# Audio.net
KiCad netlist of a schematic drawn in Altium Designer
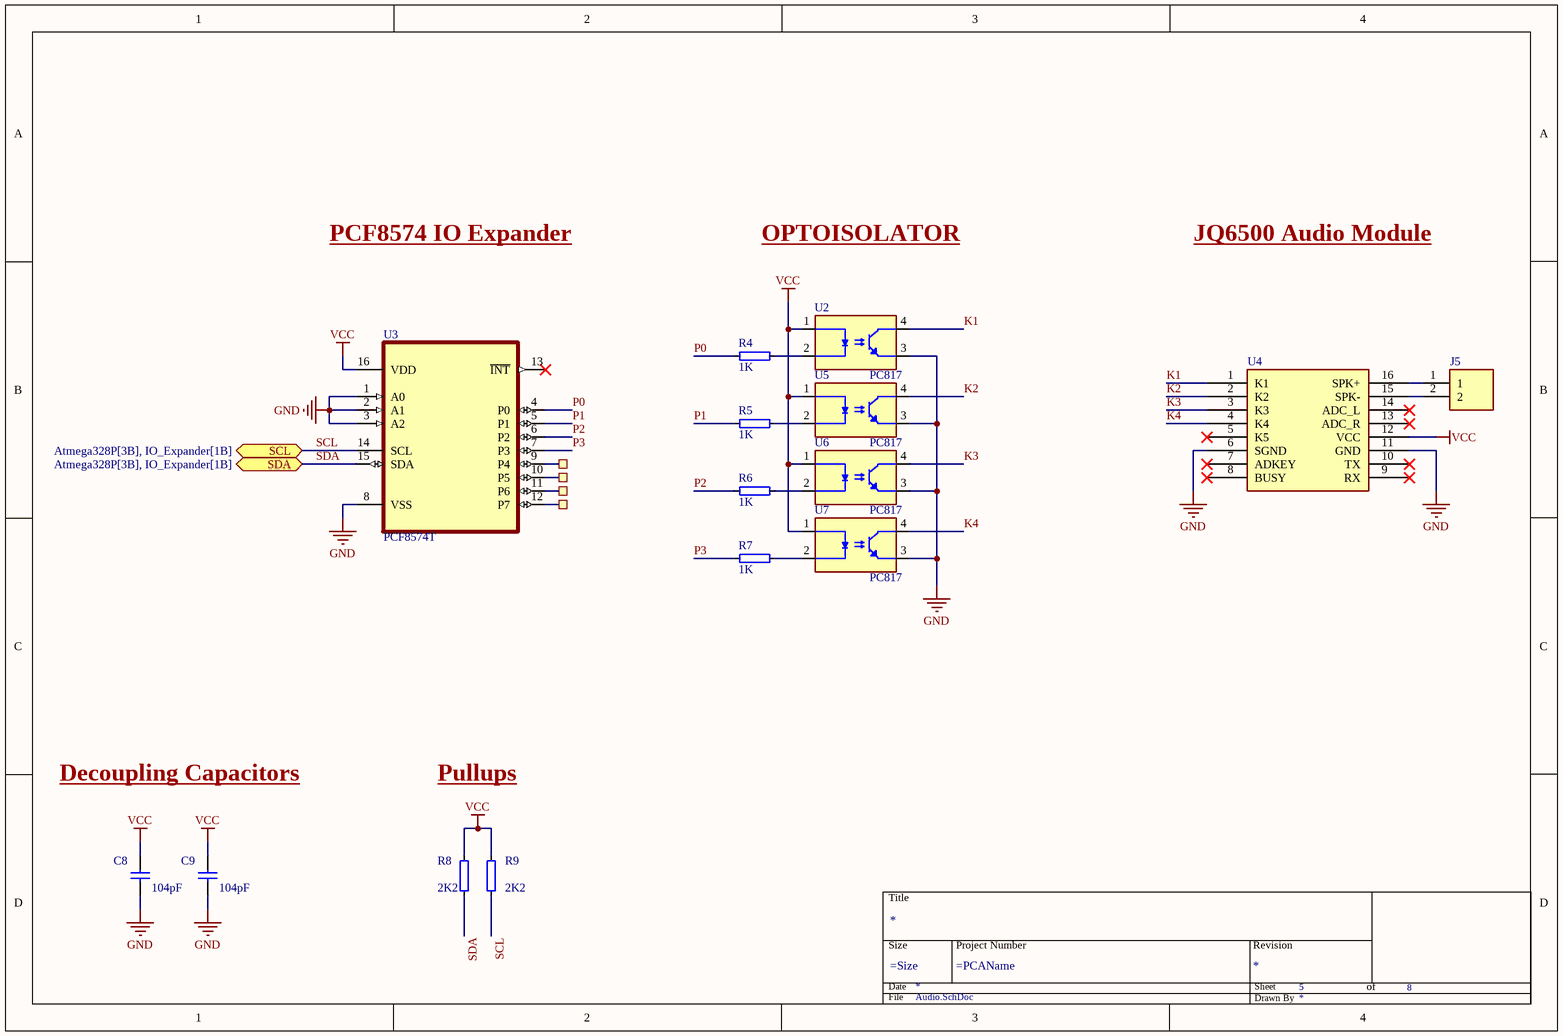
[diagram p0: Audio.SchDoc]

(export (version "E")
  (design (tool "Eeschema 10.0.6"))
  (components
    (comp (ref "*") (value "Title Block") (libsource (lib "HEPA_LIB") (part "Title Block")))
    (comp (ref "C8")
      (value "104pF")
      (footprint "CAPC2012X140N")
      (fields (field (name "PART NUMBER") "CAP_0805") (field (name "PUBLISHER") "Metal Circuits"))
      (libsource (lib "HEPA_LIB") (part "CAP_0805"))
    )
    (comp (ref "C9")
      (value "104pF")
      (footprint "CAPC2012X140N")
      (fields (field (name "PART NUMBER") "CAP_0805") (field (name "PUBLISHER") "Metal Circuits"))
      (libsource (lib "HEPA_LIB") (part "CAP_0805"))
    )
    (comp (ref "J5")
      (value "CONN HEADER VERT 2POS 2.5MM")
      (footprint "JST_B2B-XH-A(LF)(SN)")
      (description "Connector Header Through Hole 2 position 0.098\" (2.50mm)")
      (fields
        (field (name "PART NUMBER") "B2B-XH-A(LF)(SN)")
        (field (name "MANUFACTURER") "JST Sales America Inc.")
        (field (name "PUBLISHER") "Metal Circuits")
      )
      (libsource (lib "HEPA_LIB") (part "B2B-XH-A(LF)(SN)"))
    )
    (comp (ref "R4")
      (value "1K")
      (footprint "RESC2012X65N")
      (description "RES SMD 1% 1/10W 0805")
      (fields (field (name "PART NUMBER") "RES_0805") (field (name "PUBLISHER") "Metal Circuits"))
      (libsource (lib "HEPA_LIB") (part "RES_0805"))
    )
    (comp (ref "R5")
      (value "1K")
      (footprint "RESC2012X65N")
      (description "RES SMD 1% 1/10W 0805")
      (fields (field (name "PART NUMBER") "RES_0805") (field (name "PUBLISHER") "Metal Circuits"))
      (libsource (lib "HEPA_LIB") (part "RES_0805"))
    )
    (comp (ref "R6")
      (value "1K")
      (footprint "RESC2012X65N")
      (description "RES SMD 1% 1/10W 0805")
      (fields (field (name "PART NUMBER") "RES_0805") (field (name "PUBLISHER") "Metal Circuits"))
      (libsource (lib "HEPA_LIB") (part "RES_0805"))
    )
    (comp (ref "R7")
      (value "1K")
      (footprint "RESC2012X65N")
      (description "RES SMD 1% 1/10W 0805")
      (fields (field (name "PART NUMBER") "RES_0805") (field (name "PUBLISHER") "Metal Circuits"))
      (libsource (lib "HEPA_LIB") (part "RES_0805"))
    )
    (comp (ref "R8")
      (value "2K2")
      (footprint "RESC2012X65N")
      (description "RES SMD 1% 1/10W 0805")
      (fields (field (name "PART NUMBER") "RES_0805") (field (name "PUBLISHER") "Metal Circuits"))
      (libsource (lib "HEPA_LIB") (part "RES_0805"))
    )
    (comp (ref "R9")
      (value "2K2")
      (footprint "RESC2012X65N")
      (description "RES SMD 1% 1/10W 0805")
      (fields (field (name "PART NUMBER") "RES_0805") (field (name "PUBLISHER") "Metal Circuits"))
      (libsource (lib "HEPA_LIB") (part "RES_0805"))
    )
    (comp (ref "TP11")
      (value "TP")
      (footprint "TESTPAD-TH")
      (description "Testpoint, through hole")
      (fields (field (name "PART NUMBER") "Testpoint TH") (field (name "PUBLISHER") "Nordic Semiconductor"))
      (libsource (lib "HEPA_LIB") (part "TESTPAD_TH"))
    )
    (comp (ref "TP12")
      (value "TP")
      (footprint "TESTPAD-TH")
      (description "Testpoint, through hole")
      (fields (field (name "PART NUMBER") "Testpoint TH") (field (name "PUBLISHER") "Nordic Semiconductor"))
      (libsource (lib "HEPA_LIB") (part "TESTPAD_TH"))
    )
    (comp (ref "TP13")
      (value "TP")
      (footprint "TESTPAD-TH")
      (description "Testpoint, through hole")
      (fields (field (name "PART NUMBER") "Testpoint TH") (field (name "PUBLISHER") "Nordic Semiconductor"))
      (libsource (lib "HEPA_LIB") (part "TESTPAD_TH"))
    )
    (comp (ref "TP14")
      (value "TP")
      (footprint "TESTPAD-TH")
      (description "Testpoint, through hole")
      (fields (field (name "PART NUMBER") "Testpoint TH") (field (name "PUBLISHER") "Nordic Semiconductor"))
      (libsource (lib "HEPA_LIB") (part "TESTPAD_TH"))
    )
    (comp (ref "U2")
      (value "PC817")
      (footprint "DIP762W50P254L495H455Q4")
      (description "Optoisolator Transistor Output - 1 Channel 4-DIP")
      (fields (field (name "MANUFACTURER") "SHARP") (field (name "PUBLISHER") "Metal Circuits"))
      (libsource (lib "HEPA_LIB") (part "PC817"))
    )
    (comp (ref "U3")
      (value "PCF8574T")
      (footprint "SOIC127P1032X265-16N")
      (description "IC XPNDR 100KHZ I2C 16SO")
      (fields
        (field (name "PART NUMBER") "PCF8574T/3,518")
        (field (name "MANUFACTURER") "NXP")
        (field (name "PUBLISHER") "Metal Circuits")
      )
      (libsource (lib "HEPA_LIB") (part "PCF8574T/3,518"))
    )
    (comp (ref "U4")
      (value "JQ6500")
      (footprint "JQ6500")
      (description "JQ6500-16P with onboard 16Mbit (2 Mega Byte) Flash memory.")
      (fields (field (name "PUBLISHER") "Metal Circuits"))
      (libsource (lib "HEPA_LIB") (part "JQ6500"))
    )
    (comp (ref "U5")
      (value "PC817")
      (footprint "DIP762W50P254L495H455Q4")
      (description "Optoisolator Transistor Output - 1 Channel 4-DIP")
      (fields (field (name "MANUFACTURER") "SHARP") (field (name "PUBLISHER") "Metal Circuits"))
      (libsource (lib "HEPA_LIB") (part "PC817"))
    )
    (comp (ref "U6")
      (value "PC817")
      (footprint "DIP762W50P254L495H455Q4")
      (description "Optoisolator Transistor Output - 1 Channel 4-DIP")
      (fields (field (name "MANUFACTURER") "SHARP") (field (name "PUBLISHER") "Metal Circuits"))
      (libsource (lib "HEPA_LIB") (part "PC817"))
    )
    (comp (ref "U7")
      (value "PC817")
      (footprint "DIP762W50P254L495H455Q4")
      (description "Optoisolator Transistor Output - 1 Channel 4-DIP")
      (fields (field (name "MANUFACTURER") "SHARP") (field (name "PUBLISHER") "Metal Circuits"))
      (libsource (lib "HEPA_LIB") (part "PC817"))
    )
  )
  (nets
    (net (code "1") (name "/K1") (class "Default")
      (node (ref "U2") (pin "4") (pinfunction "COLLECTOR_4") (pintype "passive"))
      (node (ref "U4") (pin "1") (pinfunction "K1_1") (pintype "passive"))
    )
    (net (code "2") (name "/K2") (class "Default")
      (node (ref "U4") (pin "2") (pinfunction "K2_2") (pintype "passive"))
      (node (ref "U5") (pin "4") (pinfunction "COLLECTOR_4") (pintype "passive"))
    )
    (net (code "3") (name "/K3") (class "Default")
      (node (ref "U4") (pin "3") (pinfunction "K3_3") (pintype "passive"))
      (node (ref "U6") (pin "4") (pinfunction "COLLECTOR_4") (pintype "passive"))
    )
    (net (code "4") (name "/K4") (class "Default")
      (node (ref "U4") (pin "4") (pinfunction "K4_4") (pintype "passive"))
      (node (ref "U7") (pin "4") (pinfunction "COLLECTOR_4") (pintype "passive"))
    )
    (net (code "5") (name "/P0") (class "Default")
      (node (ref "R4") (pin "2") (pinfunction "2_2") (pintype "passive"))
      (node (ref "U3") (pin "4") (pinfunction "P0_4") (pintype "bidirectional"))
    )
    (net (code "6") (name "/P1") (class "Default")
      (node (ref "R5") (pin "2") (pinfunction "2_2") (pintype "passive"))
      (node (ref "U3") (pin "5") (pinfunction "P1_5") (pintype "bidirectional"))
    )
    (net (code "7") (name "/P2") (class "Default")
      (node (ref "R6") (pin "2") (pinfunction "2_2") (pintype "passive"))
      (node (ref "U3") (pin "6") (pinfunction "P2_6") (pintype "bidirectional"))
    )
    (net (code "8") (name "/P3") (class "Default")
      (node (ref "R7") (pin "2") (pinfunction "2_2") (pintype "passive"))
      (node (ref "U3") (pin "7") (pinfunction "P3_7") (pintype "bidirectional"))
    )
    (net (code "9") (name "/SCL") (class "Default")
      (node (ref "R9") (pin "1") (pinfunction "1_1") (pintype "passive"))
      (node (ref "U3") (pin "14") (pinfunction "SCL_14") (pintype "passive"))
    )
    (net (code "10") (name "/SDA") (class "Default")
      (node (ref "R8") (pin "1") (pinfunction "1_1") (pintype "passive"))
      (node (ref "U3") (pin "15") (pinfunction "SDA_15") (pintype "bidirectional"))
    )
    (net (code "11") (name "GND") (class "Default")
      (node (ref "C8") (pin "1") (pinfunction "1_1") (pintype "passive"))
      (node (ref "C9") (pin "1") (pinfunction "1_1") (pintype "passive"))
      (node (ref "U2") (pin "3") (pinfunction "EMITTER_3") (pintype "passive"))
      (node (ref "U3") (pin "1") (pinfunction "A0_1") (pintype "input"))
      (node (ref "U3") (pin "2") (pinfunction "A1_2") (pintype "input"))
      (node (ref "U3") (pin "3") (pinfunction "A2_3") (pintype "input"))
      (node (ref "U3") (pin "8") (pinfunction "VSS_8") (pintype "passive"))
      (node (ref "U4") (pin "11") (pinfunction "GND_11") (pintype "passive"))
      (node (ref "U4") (pin "6") (pinfunction "SGND_6") (pintype "passive"))
      (node (ref "U5") (pin "3") (pinfunction "EMITTER_3") (pintype "passive"))
      (node (ref "U6") (pin "3") (pinfunction "EMITTER_3") (pintype "passive"))
      (node (ref "U7") (pin "3") (pinfunction "EMITTER_3") (pintype "passive"))
    )
    (net (code "12") (name "Net-(U2-CATHODE)") (class "Default")
      (node (ref "R4") (pin "1") (pinfunction "1_1") (pintype "passive"))
      (node (ref "U2") (pin "2") (pinfunction "CATHODE_2") (pintype "passive"))
    )
    (net (code "13") (name "Net-(U3-P4)") (class "Default")
      (node (ref "TP11") (pin "1") (pinfunction "1_1") (pintype "passive"))
      (node (ref "U3") (pin "9") (pinfunction "P4_9") (pintype "bidirectional"))
    )
    (net (code "14") (name "Net-(U3-P5)") (class "Default")
      (node (ref "TP12") (pin "1") (pinfunction "1_1") (pintype "passive"))
      (node (ref "U3") (pin "10") (pinfunction "P5_10") (pintype "bidirectional"))
    )
    (net (code "15") (name "Net-(U3-P6)") (class "Default")
      (node (ref "TP13") (pin "1") (pinfunction "1_1") (pintype "passive"))
      (node (ref "U3") (pin "11") (pinfunction "P6_11") (pintype "bidirectional"))
    )
    (net (code "16") (name "Net-(U3-P7)") (class "Default")
      (node (ref "TP14") (pin "1") (pinfunction "1_1") (pintype "passive"))
      (node (ref "U3") (pin "12") (pinfunction "P7_12") (pintype "bidirectional"))
    )
    (net (code "17") (name "Net-(U4-SPK+)") (class "Default")
      (node (ref "J5") (pin "1") (pinfunction "1_1") (pintype "passive"))
      (node (ref "U4") (pin "16") (pinfunction "SPK+_16") (pintype "passive"))
    )
    (net (code "18") (name "Net-(U4-SPK-)") (class "Default")
      (node (ref "J5") (pin "2") (pinfunction "2_2") (pintype "passive"))
      (node (ref "U4") (pin "15") (pinfunction "SPK-_15") (pintype "passive"))
    )
    (net (code "19") (name "Net-(U5-CATHODE)") (class "Default")
      (node (ref "R5") (pin "1") (pinfunction "1_1") (pintype "passive"))
      (node (ref "U5") (pin "2") (pinfunction "CATHODE_2") (pintype "passive"))
    )
    (net (code "20") (name "Net-(U6-CATHODE)") (class "Default")
      (node (ref "R6") (pin "1") (pinfunction "1_1") (pintype "passive"))
      (node (ref "U6") (pin "2") (pinfunction "CATHODE_2") (pintype "passive"))
    )
    (net (code "21") (name "Net-(U7-CATHODE)") (class "Default")
      (node (ref "R7") (pin "1") (pinfunction "1_1") (pintype "passive"))
      (node (ref "U7") (pin "2") (pinfunction "CATHODE_2") (pintype "passive"))
    )
    (net (code "22") (name "VCC") (class "Default")
      (node (ref "C8") (pin "2") (pinfunction "2_2") (pintype "passive"))
      (node (ref "C9") (pin "2") (pinfunction "2_2") (pintype "passive"))
      (node (ref "R8") (pin "2") (pinfunction "2_2") (pintype "passive"))
      (node (ref "R9") (pin "2") (pinfunction "2_2") (pintype "passive"))
      (node (ref "U2") (pin "1") (pinfunction "ANODE_1") (pintype "passive"))
      (node (ref "U3") (pin "16") (pinfunction "VDD_16") (pintype "power_in"))
      (node (ref "U4") (pin "12") (pinfunction "VCC_12") (pintype "passive"))
      (node (ref "U5") (pin "1") (pinfunction "ANODE_1") (pintype "passive"))
      (node (ref "U6") (pin "1") (pinfunction "ANODE_1") (pintype "passive"))
      (node (ref "U7") (pin "1") (pinfunction "ANODE_1") (pintype "passive"))
    )
    (net (code "23") (name "unconnected-(U3-~{INT}-Pad13)") (class "Default")
      (node (ref "U3") (pin "13") (pinfunction "~{INT}_13") (pintype "output+no_connect"))
    )
    (net (code "24") (name "unconnected-(U4-ADC_L-Pad14)") (class "Default")
      (node (ref "U4") (pin "14") (pinfunction "ADC_L_14") (pintype "passive+no_connect"))
    )
    (net (code "25") (name "unconnected-(U4-ADC_R-Pad13)") (class "Default")
      (node (ref "U4") (pin "13") (pinfunction "ADC_R_13") (pintype "passive+no_connect"))
    )
    (net (code "26") (name "unconnected-(U4-ADKEY-Pad7)") (class "Default")
      (node (ref "U4") (pin "7") (pinfunction "ADKEY_7") (pintype "passive+no_connect"))
    )
    (net (code "27") (name "unconnected-(U4-BUSY-Pad8)") (class "Default")
      (node (ref "U4") (pin "8") (pinfunction "BUSY_8") (pintype "passive+no_connect"))
    )
    (net (code "28") (name "unconnected-(U4-K5-Pad5)") (class "Default")
      (node (ref "U4") (pin "5") (pinfunction "K5_5") (pintype "passive+no_connect"))
    )
    (net (code "29") (name "unconnected-(U4-RX-Pad9)") (class "Default")
      (node (ref "U4") (pin "9") (pinfunction "RX_9") (pintype "passive+no_connect"))
    )
    (net (code "30") (name "unconnected-(U4-TX-Pad10)") (class "Default")
      (node (ref "U4") (pin "10") (pinfunction "TX_10") (pintype "passive+no_connect"))
    )
  )
)
